# BJT_CC.net
KiCad netlist of a schematic drawn in EAGLE
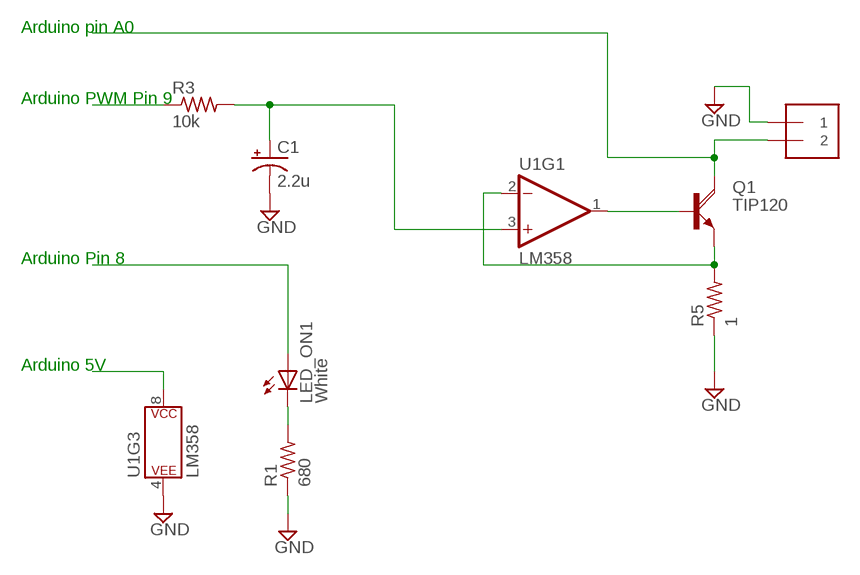
[diagram p0: schematic, sheet 1]

(export (version "E")
  (design (tool "Eeschema 10.0.6"))
  (components
    (comp (ref "BAT_IN")
      (value "1X2-3.5MM")
      (footprint "eagle-import:1X2-3.5MM")
      (libsource (lib "eagle-import") (part "1X2-3.5MM"))
    )
    (comp (ref "C1")
      (value "2.2u")
      (footprint "eagle-import:E2-4")
      (libsource (lib "eagle-import") (part "CPOL-USE2-4"))
    )
    (comp (ref "LED_ON1")
      (value "White")
      (footprint "eagle-import:LED5MM")
      (libsource (lib "eagle-import") (part "LED5MM"))
    )
    (comp (ref "Q1")
      (value "TIP120")
      (footprint "eagle-import:TO220AH")
      (libsource (lib "eagle-import") (part "TIP120"))
    )
    (comp (ref "R1")
      (value "680")
      (footprint "eagle-import:0207_10")
      (libsource (lib "eagle-import") (part "resistor_348_R-US_0207/10"))
    )
    (comp (ref "R3")
      (value "10k")
      (footprint "eagle-import:0207_10")
      (libsource (lib "eagle-import") (part "resistor_348_R-US_0207/10"))
    )
    (comp (ref "R5")
      (value "1")
      (footprint "eagle-import:0922_22")
      (libsource (lib "eagle-import") (part "R-US_0922/22"))
    )
    (comp (ref "U1")
      (value "LM358")
      (footprint "eagle-import:DIP08")
      (libsource (lib "eagle-import") (part "LM358"))
    )
  )
  (nets
    (net (code "1") (name "GND") (class "Default")
      (node (ref "BAT_IN") (pin "1") (pinfunction "1_1") (pintype "passive"))
      (node (ref "C1") (pin "-") (pinfunction "-_-") (pintype "passive"))
      (node (ref "R1") (pin "1") (pinfunction "1_1") (pintype "passive"))
      (node (ref "R5") (pin "1") (pinfunction "1_1") (pintype "passive"))
      (node (ref "U1") (pin "4") (pinfunction "P$V-_4") (pintype "bidirectional"))
    )
    (net (code "2") (name "Net-(BAT_IN-Pad2)") (class "Default")
      (node (ref "BAT_IN") (pin "2") (pinfunction "2_2") (pintype "passive"))
      (node (ref "Q1") (pin "C") (pinfunction "C_C") (pintype "passive"))
    )
    (net (code "3") (name "Net-(LED_ON1-C)") (class "Default")
      (node (ref "LED_ON1") (pin "K") (pinfunction "C_K") (pintype "passive"))
      (node (ref "R1") (pin "2") (pinfunction "2_2") (pintype "passive"))
    )
    (net (code "4") (name "Net-(U1A-+IN)") (class "Default")
      (node (ref "C1") (pin "+") (pinfunction "+_+") (pintype "passive"))
      (node (ref "R3") (pin "2") (pinfunction "2_2") (pintype "passive"))
      (node (ref "U1") (pin "3") (pinfunction "+IN_3") (pintype "input"))
    )
    (net (code "5") (name "Net-(U1A--IN)") (class "Default")
      (node (ref "Q1") (pin "E") (pinfunction "E_E") (pintype "passive"))
      (node (ref "R5") (pin "2") (pinfunction "2_2") (pintype "passive"))
      (node (ref "U1") (pin "2") (pinfunction "-IN_2") (pintype "input"))
    )
    (net (code "6") (name "Net-(U1A-OUT)") (class "Default")
      (node (ref "Q1") (pin "B") (pinfunction "B_B") (pintype "passive"))
      (node (ref "U1") (pin "1") (pinfunction "OUT_1") (pintype "output"))
    )
    (net (code "7") (name "unconnected-(LED_ON1-PadA)") (class "Default")
      (node (ref "LED_ON1") (pin "A") (pinfunction "A_A") (pintype "passive"))
    )
    (net (code "8") (name "unconnected-(R3-Pad1)") (class "Default")
      (node (ref "R3") (pin "1") (pinfunction "1_1") (pintype "passive"))
    )
    (net (code "9") (name "unconnected-(U1C-P$V+-Pad8)") (class "Default")
      (node (ref "U1") (pin "8") (pinfunction "P$V+_8") (pintype "bidirectional"))
    )
  )
)
